# Sheet4.net
KiCad netlist of a schematic drawn in Altium Designer
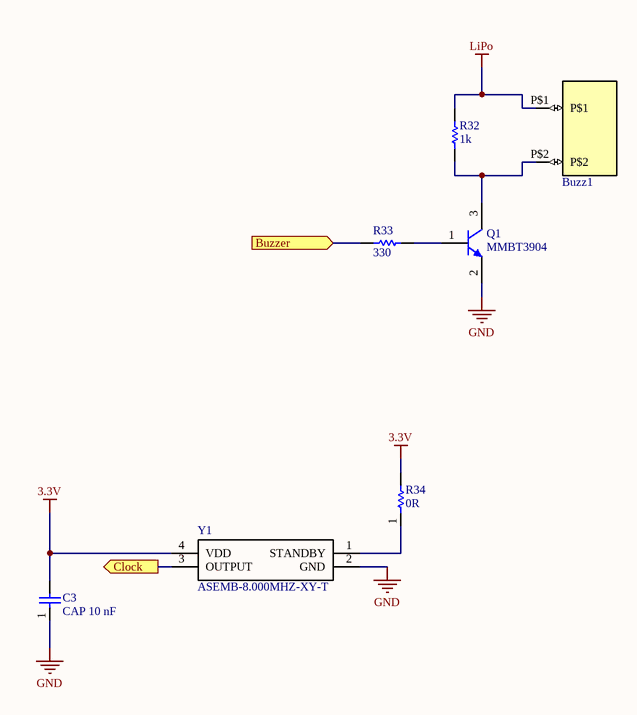
[diagram p0: Sheet4.SchDoc]

(export (version "E")
  (design (tool "Eeschema 10.0.6"))
  (components
    (comp (ref "Buzz1")
      (value "PS1240P02BT")
      (footprint "*PS1240P02BT_PS1240P02BT(Primary)")
      (description "Audio Buzzer Piezo 30Vo-p 3Vo-p 70dBA Pin Through Hole T/R")
      (fields (field (name "MF") "TDK"))
      (libsource (lib "PS1240P02BT") (part "PS1240P02BT"))
    )
    (comp (ref "C3")
      (value "CAP 10 nF")
      (footprint "06035C104KAT4A")
      (description "Capacitor")
      (fields (field (name "PUBLISHER") "Altium Limited"))
      (libsource (lib "Miscellaneous Devices") (part "Cap"))
    )
    (comp (ref "Q1")
      (value "MMBT3904")
      (footprint "FAIR-SOT23-3_V")
      (description "NPN General Purpose Amplifier, 40 V, 0.2 A, -55 to 150 degC, 3-Pin SOT23, RoHS, Tape and Reel")
      (fields (field (name "TOLERANCE") "30ppm"))
      (libsource (lib "Altium Content Vault") (part "BJT-NPN-BEC-3"))
    )
    (comp (ref "R32")
      (value "1k")
      (footprint "CR0603-J/-000ELF")
      (description "Resistor")
      (fields (field (name "PUBLISHER") "Altium Limited"))
      (libsource (lib "Miscellaneous Devices") (part "Res1"))
    )
    (comp (ref "R33")
      (value "330")
      (footprint "CR0603-J/-000ELF")
      (description "Resistor")
      (fields (field (name "PUBLISHER") "Altium Limited"))
      (libsource (lib "Miscellaneous Devices") (part "Res1"))
    )
    (comp (ref "R34")
      (value "0R")
      (footprint "CR0603-J/-000ELF")
      (description "Resistor")
      (fields (field (name "PUBLISHER") "Altium Limited"))
      (libsource (lib "") (part "Res1_1"))
    )
    (comp (ref "Y1")
      (value "ASEMB-8.000MHZ-XY-T")
      (footprint "SamacSys:ASEMB")
      (description "Crystal or Oscillator")
      (fields (field (name "MOUSER PART NUMBER") "815-ASEMB-8-XY-T"))
      (libsource (lib "*") (part "ASEMB-8.000MHZ-XY-T"))
    )
  )
  (nets
    (net (code "1") (name "/Buzzer") (class "Default")
      (node (ref "R33") (pin "1") (pinfunction "1_1") (pintype "passive"))
    )
    (net (code "2") (name "/Clock") (class "Default")
      (node (ref "Y1") (pin "3") (pinfunction "OUTPUT_3") (pintype "passive"))
    )
    (net (code "3") (name "3.3V") (class "Default")
      (node (ref "C3") (pin "2") (pinfunction "2_2") (pintype "passive"))
      (node (ref "R34") (pin "2") (pinfunction "2_2") (pintype "passive"))
      (node (ref "Y1") (pin "4") (pinfunction "VDD_4") (pintype "passive"))
    )
    (net (code "4") (name "GND") (class "Default")
      (node (ref "C3") (pin "1") (pinfunction "1_1") (pintype "passive"))
      (node (ref "Q1") (pin "2") (pinfunction "E_2") (pintype "passive"))
      (node (ref "Y1") (pin "2") (pinfunction "GND_2") (pintype "passive"))
    )
    (net (code "5") (name "LiPo") (class "Default")
      (node (ref "Buzz1") (pin "P$1") (pinfunction "P$1_P$1") (pintype "bidirectional"))
      (node (ref "R32") (pin "2") (pinfunction "2_2") (pintype "passive"))
    )
    (net (code "6") (name "Net-(Q1-B)") (class "Default")
      (node (ref "Q1") (pin "1") (pinfunction "B_1") (pintype "passive"))
      (node (ref "R33") (pin "2") (pinfunction "2_2") (pintype "passive"))
    )
    (net (code "7") (name "Net-(Q1-C)") (class "Default")
      (node (ref "Buzz1") (pin "P$2") (pinfunction "P$2_P$2") (pintype "bidirectional"))
      (node (ref "Q1") (pin "3") (pinfunction "C_3") (pintype "passive"))
      (node (ref "R32") (pin "1") (pinfunction "1_1") (pintype "passive"))
    )
    (net (code "8") (name "Net-(Y1-STANDBY)") (class "Default")
      (node (ref "R34") (pin "1") (pinfunction "1_1") (pintype "passive"))
      (node (ref "Y1") (pin "1") (pinfunction "STANDBY_1") (pintype "passive"))
    )
  )
)
